# 1_0.net
KiCad netlist of a schematic drawn in Altium Designer
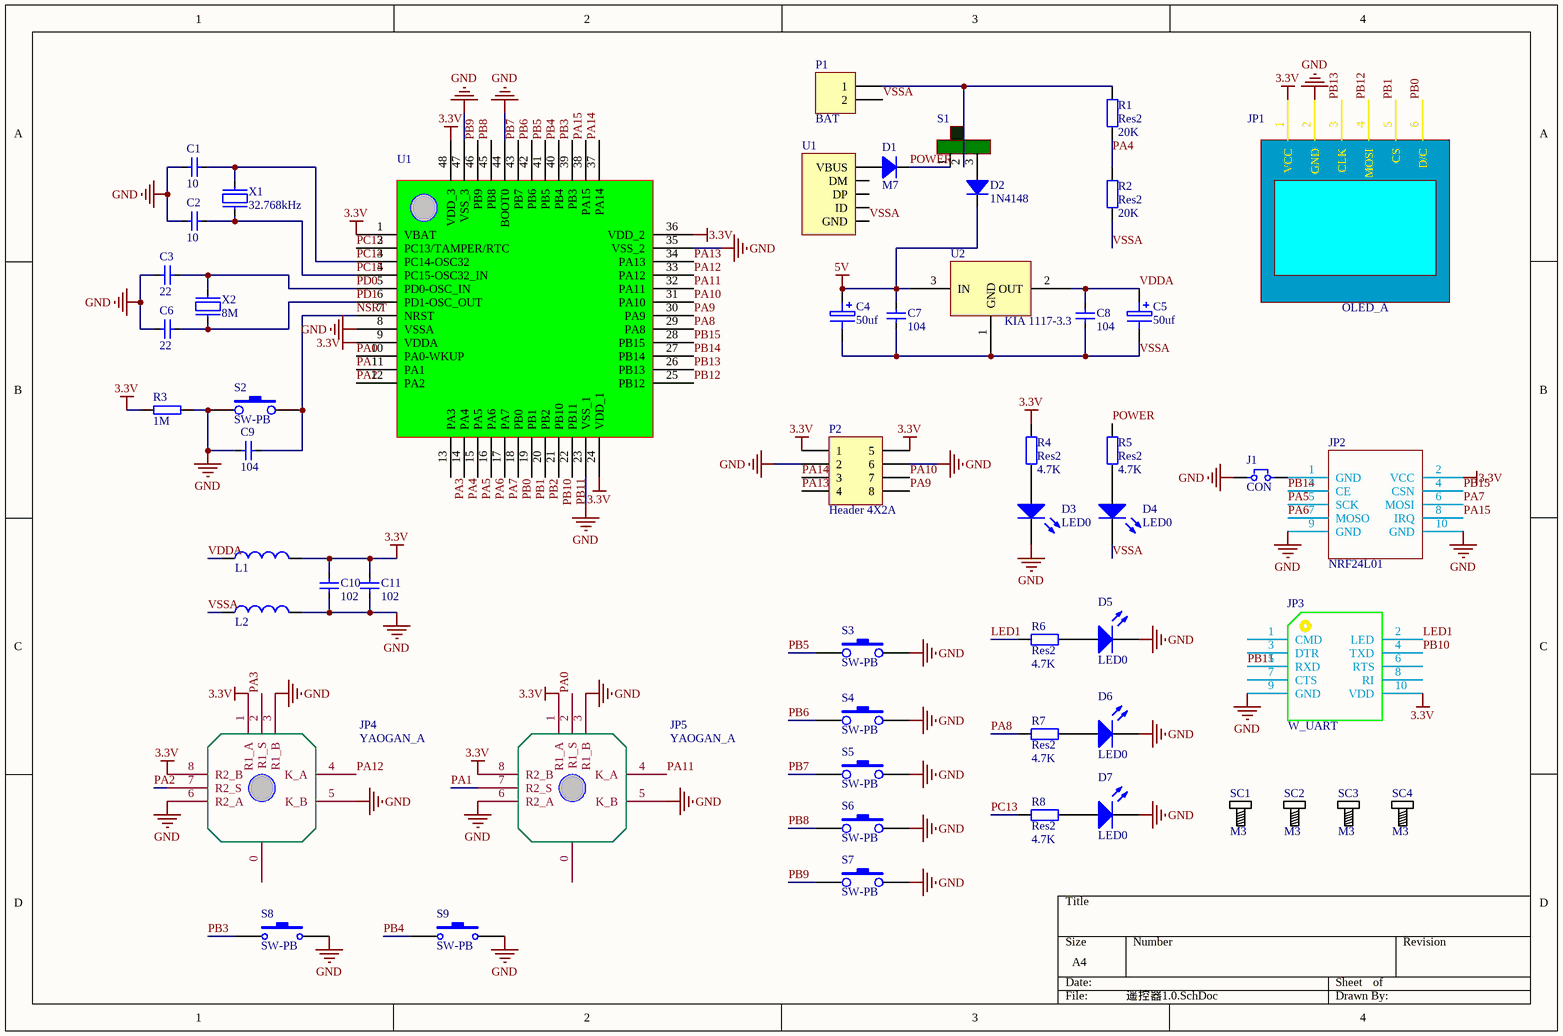
[diagram p0: 遥控器1.0.SchDoc]

(export (version "E")
  (design (tool "Eeschema 10.0.6"))
  (components
    (comp (ref "C1")
      (value "CAP_22")
      (footprint "0805-C")
      (fields (field (name "ALTIUM_UNNAMED_1") "10"))
      (libsource (lib "Flyking 常用元件") (part "CAP_22"))
    )
    (comp (ref "C2")
      (value "CAP_22")
      (footprint "0805-C")
      (fields (field (name "ALTIUM_UNNAMED_1") "10"))
      (libsource (lib "Flyking 常用元件") (part "CAP_22"))
    )
    (comp (ref "C3")
      (value "CAP_22")
      (footprint "0805-C")
      (fields (field (name "ALTIUM_UNNAMED_1") "22"))
      (libsource (lib "Flyking 常用元件") (part "CAP_22"))
    )
    (comp (ref "C4")
      (value "CAPE_10uf")
      (footprint "CAP_7*7")
      (fields (field (name "ALTIUM_UNNAMED_1") "50uf"))
      (libsource (lib "Flyking 常用元件") (part "CAPE_10uf"))
    )
    (comp (ref "C5")
      (value "CAPE_10uf")
      (footprint "CAP_7*7")
      (fields (field (name "ALTIUM_UNNAMED_1") "50uf"))
      (libsource (lib "Flyking 常用元件") (part "CAPE_10uf"))
    )
    (comp (ref "C6")
      (value "CAP_22")
      (footprint "0805-C")
      (fields (field (name "ALTIUM_UNNAMED_1") "22"))
      (libsource (lib "Flyking 常用元件") (part "CAP_22"))
    )
    (comp (ref "C7")
      (value "CAP_22")
      (footprint "0805-C")
      (fields (field (name "ALTIUM_UNNAMED_1") "104"))
      (libsource (lib "Flyking 常用元件") (part "CAP_22"))
    )
    (comp (ref "C8")
      (value "CAP_22")
      (footprint "0805-C")
      (fields (field (name "ALTIUM_UNNAMED_1") "104"))
      (libsource (lib "Flyking 常用元件") (part "CAP_22"))
    )
    (comp (ref "C9")
      (value "CAP_22")
      (footprint "0805-C")
      (fields (field (name "ALTIUM_UNNAMED_1") "104"))
      (libsource (lib "Flyking 常用元件") (part "CAP_22"))
    )
    (comp (ref "C10")
      (value "CAP_22")
      (footprint "0805-C")
      (fields (field (name "ALTIUM_UNNAMED_1") "102"))
      (libsource (lib "Flyking 常用元件") (part "CAP_22"))
    )
    (comp (ref "C11")
      (value "CAP_22")
      (footprint "0805-C")
      (fields (field (name "ALTIUM_UNNAMED_1") "102"))
      (libsource (lib "Flyking 常用元件") (part "CAP_22"))
    )
    (comp (ref "D1") (value "M7") (footprint "D_214A") (libsource (lib "xl_lib_v_2") (part "1N4148")))
    (comp (ref "D2") (value "1N4148") (footprint "D_214A") (libsource (lib "xl_lib_v_2") (part "1N4148")))
    (comp (ref "D3")
      (value "LED0")
      (footprint "0805-LED")
      (description "Typical INFRARED GaAs LED")
      (fields (field (name "PUBLISHER") "Altium Limited"))
      (libsource (lib "Miscellaneous Devices") (part "LED0"))
    )
    (comp (ref "D4")
      (value "LED0")
      (footprint "0805-LED")
      (description "Typical INFRARED GaAs LED")
      (fields (field (name "PUBLISHER") "Altium Limited"))
      (libsource (lib "Miscellaneous Devices") (part "LED0"))
    )
    (comp (ref "D5")
      (value "LED0")
      (footprint "0805-LED")
      (description "Typical INFRARED GaAs LED")
      (fields (field (name "PUBLISHER") "Altium Limited"))
      (libsource (lib "Miscellaneous Devices") (part "LED0"))
    )
    (comp (ref "D6")
      (value "LED0")
      (footprint "0805-LED")
      (description "Typical INFRARED GaAs LED")
      (fields (field (name "PUBLISHER") "Altium Limited"))
      (libsource (lib "Miscellaneous Devices") (part "LED0"))
    )
    (comp (ref "D7")
      (value "LED0")
      (footprint "0805-LED")
      (description "Typical INFRARED GaAs LED")
      (fields (field (name "PUBLISHER") "Altium Limited"))
      (libsource (lib "Miscellaneous Devices") (part "LED0"))
    )
    (comp (ref "J1")
      (value "CON")
      (footprint "HDR1X2-2.54")
      (libsource (lib "xl_lib_v_1") (part "JAP-HEADER2"))
    )
    (comp (ref "JP1") (value "OLED_A") (footprint "OLED-18*17") (libsource (lib "OLED") (part "OLED_A")))
    (comp (ref "JP2")
      (value "NRF24L01")
      (footprint "NRF24L01_A")
      (libsource (lib "NRF24L01") (part "NRF24L01"))
    )
    (comp (ref "JP3") (value "W_UART") (footprint "S-UART") (libsource (lib "S_USRT") (part "W_UART")))
    (comp (ref "JP4")
      (value "YAOGAN_A")
      (footprint "YAOGAN_A")
      (libsource (lib "SCH_IPC7_LC") (part "YAOGAN_A"))
    )
    (comp (ref "JP5")
      (value "YAOGAN_A")
      (footprint "YAOGAN_A")
      (libsource (lib "SCH_IPC7_LC") (part "YAOGAN_A"))
    )
    (comp (ref "L1") (value "L_") (footprint "0805") (libsource (lib "Flyking 常用元件") (part "L_")))
    (comp (ref "L2") (value "L_") (footprint "0805") (libsource (lib "Flyking 常用元件") (part "L_")))
    (comp (ref "P1")
      (value "BAT")
      (footprint "3.2X1.6X1.1")
      (description "Header, 2-Pin")
      (fields (field (name "PUBLISHER") "Altium Limited"))
      (libsource (lib "Miscellaneous Connectors") (part "Header 2"))
    )
    (comp (ref "P2")
      (value "Header 4X2A")
      (footprint "HDR2X4_CEN")
      (description "Header, 4-Pin, Dual row")
      (fields (field (name "PUBLISHER") "Altium Limited"))
      (libsource (lib "Miscellaneous Connectors") (part "Header 4X2A"))
    )
    (comp (ref "R1")
      (value "Res2")
      (footprint "0805-R")
      (description "Resistor")
      (fields (field (name "ALTIUM_VALUE") "20K") (field (name "PUBLISHER") "Altium Limited"))
      (libsource (lib "Miscellaneous Devices") (part "Res2"))
    )
    (comp (ref "R2")
      (value "Res2")
      (footprint "0805-R")
      (description "Resistor")
      (fields (field (name "ALTIUM_VALUE") "20K") (field (name "PUBLISHER") "Altium Limited"))
      (libsource (lib "Miscellaneous Devices") (part "Res2"))
    )
    (comp (ref "R3")
      (value "RES_10K")
      (footprint "0805-R")
      (fields (field (name "ALTIUM_UNNAMED_1") "1M"))
      (libsource (lib "Flyking 常用元件") (part "RES_10K"))
    )
    (comp (ref "R4")
      (value "Res2")
      (footprint "0805-R")
      (description "Resistor")
      (fields (field (name "ALTIUM_VALUE") "4.7K") (field (name "PUBLISHER") "Altium Limited"))
      (libsource (lib "") (part "Res2_1"))
    )
    (comp (ref "R5")
      (value "Res2")
      (footprint "0805-R")
      (description "Resistor")
      (fields (field (name "ALTIUM_VALUE") "4.7K") (field (name "PUBLISHER") "Altium Limited"))
      (libsource (lib "") (part "Res2_1"))
    )
    (comp (ref "R6")
      (value "Res2")
      (footprint "0805-R")
      (description "Resistor")
      (fields (field (name "ALTIUM_VALUE") "4.7K") (field (name "PUBLISHER") "Altium Limited"))
      (libsource (lib "") (part "Res2_2"))
    )
    (comp (ref "R7")
      (value "Res2")
      (footprint "0805-R")
      (description "Resistor")
      (fields (field (name "ALTIUM_VALUE") "4.7K") (field (name "PUBLISHER") "Altium Limited"))
      (libsource (lib "") (part "Res2_2"))
    )
    (comp (ref "R8")
      (value "Res2")
      (footprint "0805-R")
      (description "Resistor")
      (fields (field (name "ALTIUM_VALUE") "4.7K") (field (name "PUBLISHER") "Altium Limited"))
      (libsource (lib "") (part "Res2_2"))
    )
    (comp (ref "S1")
      (value "SS12D07-1P2T")
      (footprint "SS12D07-1")
      (libsource (lib "xl_lib_v_1") (part "SS12D07"))
    )
    (comp (ref "S2") (value "SW-PB") (footprint "SW-SMD-T") (libsource (lib "SW开关") (part "SW-PB")))
    (comp (ref "S3") (value "SW-PB") (footprint "KEY-SMD") (libsource (lib "SW开关") (part "SW-PB")))
    (comp (ref "S4") (value "SW-PB") (footprint "KEY-SMD") (libsource (lib "SW开关") (part "SW-PB")))
    (comp (ref "S5") (value "SW-PB") (footprint "KEY-SMD") (libsource (lib "SW开关") (part "SW-PB")))
    (comp (ref "S6") (value "SW-PB") (footprint "KEY-SMD") (libsource (lib "SW开关") (part "SW-PB")))
    (comp (ref "S7") (value "SW-PB") (footprint "KEY-SMD") (libsource (lib "SW开关") (part "SW-PB")))
    (comp (ref "S8")
      (value "SW-PB")
      (footprint "KEY-4B")
      (description "Switch")
      (fields (field (name "PUBLISHER") "Altium Limited"))
      (libsource (lib "Miscellaneous Devices") (part "SW-PB"))
    )
    (comp (ref "S9")
      (value "SW-PB")
      (footprint "KEY-4B")
      (description "Switch")
      (fields (field (name "PUBLISHER") "Altium Limited"))
      (libsource (lib "Miscellaneous Devices") (part "SW-PB"))
    )
    (comp (ref "SC1")
      (value "M3")
      (footprint "TZ-M3")
      (description "Screw")
      (libsource (lib "SCH_Other") (part "Screw_M3"))
    )
    (comp (ref "SC2")
      (value "M3")
      (footprint "TZ-M3")
      (description "Screw")
      (libsource (lib "SCH_Other") (part "Screw_M3"))
    )
    (comp (ref "SC3")
      (value "M3")
      (footprint "TZ-M3")
      (description "Screw")
      (libsource (lib "SCH_Other") (part "Screw_M3"))
    )
    (comp (ref "SC4")
      (value "M3")
      (footprint "TZ-M3")
      (description "Screw")
      (libsource (lib "SCH_Other") (part "Screw_M3"))
    )
    (comp (ref "U1")
      (value "USB_Micro")
      (footprint "USB_MINI_B")
      (description "USB")
      (libsource (lib "SCH_USB") (part "USB_Micro"))
    )
    (comp (ref "U2")
      (value "KIA 1117-3.3")
      (footprint "SOT-223")
      (fields (field (name "ALTIUM_UNNAMED_1") "KIA 1117-3.3"))
      (libsource (lib "Flyking 常用元件") (part "KIA 1117-3.3"))
    )
    (comp (ref "U3")
      (value "U1")
      (footprint "LQFP48_L")
      (description "STM32F103C8T6")
      (libsource (lib "STM32F103C8T6") (part "Component_1"))
    )
    (comp (ref "X1")
      (value "XTAL")
      (footprint "XO-3*8")
      (fields (field (name "ALTIUM_UNNAMED_1") "32.768kHz"))
      (libsource (lib "Flyking 常用元件") (part "XTAL"))
    )
    (comp (ref "X2")
      (value "XTAL")
      (footprint "HC-49")
      (fields (field (name "ALTIUM_UNNAMED_1") "8M"))
      (libsource (lib "Flyking 常用元件") (part "XTAL"))
    )
  )
  (nets
    (net (code "1") (name "/LED1") (class "Default")
      (node (ref "JP3") (pin "2") (pinfunction "LED_2") (pintype "passive"))
      (node (ref "R6") (pin "1") (pinfunction "1_1") (pintype "passive"))
    )
    (net (code "2") (name "/NSRT") (class "Default")
      (node (ref "C9") (pin "2") (pintype "passive"))
      (node (ref "S2") (pin "2") (pinfunction "2_2") (pintype "passive"))
      (node (ref "U3") (pin "7") (pinfunction "NRST_7") (pintype "passive"))
    )
    (net (code "3") (name "/PA0") (class "Default")
      (node (ref "JP5") (pin "2") (pinfunction "R1_S_2") (pintype "passive"))
      (node (ref "U3") (pin "10") (pinfunction "PA0-WKUP_10") (pintype "passive"))
    )
    (net (code "4") (name "/PA1") (class "Default")
      (node (ref "JP5") (pin "7") (pinfunction "R2_S_7") (pintype "passive"))
      (node (ref "U3") (pin "11") (pinfunction "PA1_11") (pintype "passive"))
    )
    (net (code "5") (name "/PA2") (class "Default")
      (node (ref "JP4") (pin "7") (pinfunction "R2_S_7") (pintype "passive"))
      (node (ref "U3") (pin "12") (pinfunction "PA2_12") (pintype "passive"))
    )
    (net (code "6") (name "/PA3") (class "Default")
      (node (ref "JP4") (pin "2") (pinfunction "R1_S_2") (pintype "passive"))
      (node (ref "U3") (pin "13") (pinfunction "PA3_13") (pintype "passive"))
    )
    (net (code "7") (name "/PA4") (class "Default")
      (node (ref "R1") (pin "1") (pinfunction "1_1") (pintype "passive"))
      (node (ref "R2") (pin "2") (pinfunction "2_2") (pintype "passive"))
      (node (ref "U3") (pin "14") (pinfunction "PA4_14") (pintype "passive"))
    )
    (net (code "8") (name "/PA5") (class "Default")
      (node (ref "JP2") (pin "5") (pinfunction "SCK_5") (pintype "passive"))
      (node (ref "U3") (pin "15") (pinfunction "PA5_15") (pintype "passive"))
    )
    (net (code "9") (name "/PA6") (class "Default")
      (node (ref "JP2") (pin "7") (pinfunction "MOSO_7") (pintype "passive"))
      (node (ref "U3") (pin "16") (pinfunction "PA6_16") (pintype "passive"))
    )
    (net (code "10") (name "/PA7") (class "Default")
      (node (ref "JP2") (pin "6") (pinfunction "MOSI_6") (pintype "passive"))
      (node (ref "U3") (pin "17") (pinfunction "PA7_17") (pintype "passive"))
    )
    (net (code "11") (name "/PA8") (class "Default")
      (node (ref "R7") (pin "1") (pinfunction "1_1") (pintype "passive"))
      (node (ref "U3") (pin "29") (pinfunction "PA8_29") (pintype "passive"))
    )
    (net (code "12") (name "/PA9") (class "Default")
      (node (ref "P2") (pin "8") (pinfunction "8_8") (pintype "passive"))
      (node (ref "U3") (pin "30") (pinfunction "PA9_30") (pintype "passive"))
    )
    (net (code "13") (name "/PA10") (class "Default")
      (node (ref "P2") (pin "7") (pinfunction "7_7") (pintype "passive"))
      (node (ref "U3") (pin "31") (pinfunction "PA10_31") (pintype "passive"))
    )
    (net (code "14") (name "/PA11") (class "Default")
      (node (ref "JP5") (pin "4") (pinfunction "K_A_4") (pintype "passive"))
      (node (ref "U3") (pin "32") (pinfunction "PA11_32") (pintype "passive"))
    )
    (net (code "15") (name "/PA12") (class "Default")
      (node (ref "JP4") (pin "4") (pinfunction "K_A_4") (pintype "passive"))
      (node (ref "U3") (pin "33") (pinfunction "PA12_33") (pintype "passive"))
    )
    (net (code "16") (name "/PA13") (class "Default")
      (node (ref "P2") (pin "4") (pinfunction "4_4") (pintype "passive"))
      (node (ref "U3") (pin "34") (pinfunction "PA13_34") (pintype "passive"))
    )
    (net (code "17") (name "/PA14") (class "Default")
      (node (ref "P2") (pin "3") (pinfunction "3_3") (pintype "passive"))
      (node (ref "U3") (pin "37") (pinfunction "PA14_37") (pintype "passive"))
    )
    (net (code "18") (name "/PA15") (class "Default")
      (node (ref "JP2") (pin "8") (pinfunction "IRQ_8") (pintype "passive"))
      (node (ref "U3") (pin "38") (pinfunction "PA15_38") (pintype "passive"))
    )
    (net (code "19") (name "/PB0") (class "Default")
      (node (ref "JP1") (pin "6") (pinfunction "D/C_6") (pintype "passive"))
      (node (ref "U3") (pin "18") (pinfunction "PB0_18") (pintype "passive"))
    )
    (net (code "20") (name "/PB1") (class "Default")
      (node (ref "JP1") (pin "5") (pinfunction "CS_5") (pintype "passive"))
      (node (ref "U3") (pin "19") (pinfunction "PB1_19") (pintype "passive"))
    )
    (net (code "21") (name "/PB2") (class "Default")
      (node (ref "U3") (pin "20") (pinfunction "PB2_20") (pintype "passive"))
    )
    (net (code "22") (name "/PB3") (class "Default")
      (node (ref "S8") (pin "1") (pinfunction "1_1") (pintype "passive"))
      (node (ref "U3") (pin "39") (pinfunction "PB3_39") (pintype "passive"))
    )
    (net (code "23") (name "/PB4") (class "Default")
      (node (ref "S9") (pin "1") (pinfunction "1_1") (pintype "passive"))
      (node (ref "U3") (pin "40") (pinfunction "PB4_40") (pintype "passive"))
    )
    (net (code "24") (name "/PB5") (class "Default")
      (node (ref "S3") (pin "1") (pinfunction "1_1") (pintype "passive"))
      (node (ref "U3") (pin "41") (pinfunction "PB5_41") (pintype "passive"))
    )
    (net (code "25") (name "/PB6") (class "Default")
      (node (ref "S4") (pin "1") (pinfunction "1_1") (pintype "passive"))
      (node (ref "U3") (pin "42") (pinfunction "PB6_42") (pintype "passive"))
    )
    (net (code "26") (name "/PB7") (class "Default")
      (node (ref "S5") (pin "1") (pinfunction "1_1") (pintype "passive"))
      (node (ref "U3") (pin "43") (pinfunction "PB7_43") (pintype "passive"))
    )
    (net (code "27") (name "/PB8") (class "Default")
      (node (ref "S6") (pin "1") (pinfunction "1_1") (pintype "passive"))
      (node (ref "U3") (pin "45") (pinfunction "PB8_45") (pintype "passive"))
    )
    (net (code "28") (name "/PB9") (class "Default")
      (node (ref "S7") (pin "1") (pinfunction "1_1") (pintype "passive"))
      (node (ref "U3") (pin "46") (pinfunction "PB9_46") (pintype "passive"))
    )
    (net (code "29") (name "/PB10") (class "Default")
      (node (ref "JP3") (pin "4") (pinfunction "TXD_4") (pintype "passive"))
      (node (ref "U3") (pin "21") (pinfunction "PB10_21") (pintype "passive"))
    )
    (net (code "30") (name "/PB11") (class "Default")
      (node (ref "JP3") (pin "5") (pinfunction "RXD_5") (pintype "passive"))
      (node (ref "U3") (pin "22") (pinfunction "PB11_22") (pintype "passive"))
    )
    (net (code "31") (name "/PB12") (class "Default")
      (node (ref "JP1") (pin "4") (pinfunction "MOSI_4") (pintype "passive"))
      (node (ref "U3") (pin "25") (pinfunction "PB12_25") (pintype "passive"))
    )
    (net (code "32") (name "/PB13") (class "Default")
      (node (ref "JP1") (pin "3") (pinfunction "CLK_3") (pintype "passive"))
      (node (ref "U3") (pin "26") (pinfunction "PB13_26") (pintype "passive"))
    )
    (net (code "33") (name "/PB14") (class "Default")
      (node (ref "JP2") (pin "3") (pinfunction "CE_3") (pintype "passive"))
      (node (ref "U3") (pin "27") (pinfunction "PB14_27") (pintype "passive"))
    )
    (net (code "34") (name "/PB15") (class "Default")
      (node (ref "JP2") (pin "4") (pinfunction "CSN_4") (pintype "passive"))
      (node (ref "U3") (pin "28") (pinfunction "PB15_28") (pintype "passive"))
    )
    (net (code "35") (name "/PC13") (class "Default")
      (node (ref "R8") (pin "1") (pinfunction "1_1") (pintype "passive"))
      (node (ref "U3") (pin "2") (pinfunction "PC13/TAMPER/RTC_2") (pintype "passive"))
    )
    (net (code "36") (name "/PC14") (class "Default")
      (node (ref "C1") (pin "2") (pintype "passive"))
      (node (ref "U3") (pin "3") (pinfunction "PC14-OSC32_3") (pintype "passive"))
      (node (ref "X1") (pin "2") (pintype "passive"))
    )
    (net (code "37") (name "/PC15") (class "Default")
      (node (ref "C2") (pin "2") (pintype "passive"))
      (node (ref "U3") (pin "4") (pinfunction "PC15-OSC32_IN_4") (pintype "passive"))
      (node (ref "X1") (pin "1") (pintype "passive"))
    )
    (net (code "38") (name "/PD0") (class "Default")
      (node (ref "C3") (pin "2") (pintype "passive"))
      (node (ref "U3") (pin "5") (pinfunction "PD0-OSC_IN_5") (pintype "passive"))
      (node (ref "X2") (pin "2") (pintype "passive"))
    )
    (net (code "39") (name "/PD1") (class "Default")
      (node (ref "C6") (pin "2") (pintype "passive"))
      (node (ref "U3") (pin "6") (pinfunction "PD1-OSC_OUT_6") (pintype "passive"))
      (node (ref "X2") (pin "1") (pintype "passive"))
    )
    (net (code "40") (name "/POWER") (class "Default")
      (node (ref "D1") (pin "2") (pinfunction "K_2") (pintype "passive"))
      (node (ref "R5") (pin "1") (pinfunction "1_1") (pintype "passive"))
      (node (ref "S1") (pin "1") (pinfunction "S1_1") (pintype "passive"))
    )
    (net (code "41") (name "/VDDA") (class "Default")
      (node (ref "C5") (pin "1") (pinfunction "+_1") (pintype "passive"))
      (node (ref "C8") (pin "2") (pintype "passive"))
      (node (ref "L1") (pin "1") (pinfunction "1_1") (pintype "passive"))
      (node (ref "U2") (pin "2") (pinfunction "OUT_2") (pintype "passive"))
    )
    (net (code "42") (name "/VSSA") (class "Default")
      (node (ref "C4") (pin "2") (pinfunction "--_2") (pintype "passive"))
      (node (ref "C5") (pin "2") (pinfunction "--_2") (pintype "passive"))
      (node (ref "C7") (pin "1") (pintype "passive"))
      (node (ref "C8") (pin "1") (pintype "passive"))
      (node (ref "D4") (pin "2") (pinfunction "K_2") (pintype "passive"))
      (node (ref "L2") (pin "1") (pinfunction "1_1") (pintype "passive"))
      (node (ref "P1") (pin "2") (pinfunction "2_2") (pintype "passive"))
      (node (ref "R2") (pin "1") (pinfunction "1_1") (pintype "passive"))
      (node (ref "U1") (pin "5") (pinfunction "GND_5") (pintype "passive"))
      (node (ref "U2") (pin "1") (pinfunction "GND_1") (pintype "passive"))
    )
    (net (code "43") (name "3.3V") (class "Default")
      (node (ref "C10") (pin "2") (pintype "passive"))
      (node (ref "C11") (pin "2") (pintype "passive"))
      (node (ref "JP1") (pin "1") (pinfunction "VCC_1") (pintype "passive"))
      (node (ref "JP2") (pin "2") (pinfunction "VCC_2") (pintype "passive"))
      (node (ref "JP3") (pin "10") (pinfunction "VDD_10") (pintype "passive"))
      (node (ref "JP4") (pin "1") (pinfunction "R1_A_1") (pintype "passive"))
      (node (ref "JP4") (pin "8") (pinfunction "R2_B_8") (pintype "passive"))
      (node (ref "JP5") (pin "1") (pinfunction "R1_A_1") (pintype "passive"))
      (node (ref "JP5") (pin "8") (pinfunction "R2_B_8") (pintype "passive"))
      (node (ref "L1") (pin "2") (pinfunction "2_2") (pintype "passive"))
      (node (ref "P2") (pin "1") (pinfunction "1_1") (pintype "passive"))
      (node (ref "P2") (pin "5") (pinfunction "5_5") (pintype "passive"))
      (node (ref "R3") (pin "2") (pintype "passive"))
      (node (ref "R4") (pin "1") (pinfunction "1_1") (pintype "passive"))
      (node (ref "U3") (pin "1") (pinfunction "VBAT_1") (pintype "passive"))
      (node (ref "U3") (pin "24") (pinfunction "VDD_1_24") (pintype "passive"))
      (node (ref "U3") (pin "36") (pinfunction "VDD_2_36") (pintype "passive"))
      (node (ref "U3") (pin "48") (pinfunction "VDD_3_48") (pintype "passive"))
      (node (ref "U3") (pin "9") (pinfunction "VDDA_9") (pintype "passive"))
    )
    (net (code "44") (name "5V") (class "Default")
      (node (ref "C4") (pin "1") (pinfunction "+_1") (pintype "passive"))
      (node (ref "C7") (pin "2") (pintype "passive"))
      (node (ref "D2") (pin "2") (pinfunction "K_2") (pintype "passive"))
      (node (ref "U2") (pin "3") (pinfunction "IN_3") (pintype "passive"))
    )
    (net (code "45") (name "GND") (class "Default")
      (node (ref "C1") (pin "1") (pintype "passive"))
      (node (ref "C10") (pin "1") (pintype "passive"))
      (node (ref "C11") (pin "1") (pintype "passive"))
      (node (ref "C2") (pin "1") (pintype "passive"))
      (node (ref "C3") (pin "1") (pintype "passive"))
      (node (ref "C6") (pin "1") (pintype "passive"))
      (node (ref "C9") (pin "1") (pintype "passive"))
      (node (ref "D3") (pin "2") (pinfunction "K_2") (pintype "passive"))
      (node (ref "D5") (pin "2") (pinfunction "K_2") (pintype "passive"))
      (node (ref "D6") (pin "2") (pinfunction "K_2") (pintype "passive"))
      (node (ref "D7") (pin "2") (pinfunction "K_2") (pintype "passive"))
      (node (ref "J1") (pin "1") (pinfunction "1_1") (pintype "passive"))
      (node (ref "JP1") (pin "2") (pinfunction "GND_2") (pintype "passive"))
      (node (ref "JP2") (pin "10") (pinfunction "GND_10") (pintype "passive"))
      (node (ref "JP2") (pin "9") (pinfunction "GND_9") (pintype "passive"))
      (node (ref "JP3") (pin "9") (pinfunction "GND_9") (pintype "passive"))
      (node (ref "JP4") (pin "3") (pinfunction "R1_B_3") (pintype "passive"))
      (node (ref "JP4") (pin "5") (pinfunction "K_B_5") (pintype "passive"))
      (node (ref "JP4") (pin "6") (pinfunction "R2_A_6") (pintype "passive"))
      (node (ref "JP5") (pin "3") (pinfunction "R1_B_3") (pintype "passive"))
      (node (ref "JP5") (pin "5") (pinfunction "K_B_5") (pintype "passive"))
      (node (ref "JP5") (pin "6") (pinfunction "R2_A_6") (pintype "passive"))
      (node (ref "L2") (pin "2") (pinfunction "2_2") (pintype "passive"))
      (node (ref "P2") (pin "2") (pinfunction "2_2") (pintype "passive"))
      (node (ref "P2") (pin "6") (pinfunction "6_6") (pintype "passive"))
      (node (ref "R3") (pin "1") (pintype "passive"))
      (node (ref "S2") (pin "1") (pinfunction "1_1") (pintype "passive"))
      (node (ref "S3") (pin "2") (pinfunction "2_2") (pintype "passive"))
      (node (ref "S4") (pin "2") (pinfunction "2_2") (pintype "passive"))
      (node (ref "S5") (pin "2") (pinfunction "2_2") (pintype "passive"))
      (node (ref "S6") (pin "2") (pinfunction "2_2") (pintype "passive"))
      (node (ref "S7") (pin "2") (pinfunction "2_2") (pintype "passive"))
      (node (ref "S8") (pin "2") (pinfunction "2_2") (pintype "passive"))
      (node (ref "S9") (pin "2") (pinfunction "2_2") (pintype "passive"))
      (node (ref "U3") (pin "23") (pinfunction "VSS_1_23") (pintype "passive"))
      (node (ref "U3") (pin "35") (pinfunction "VSS_2_35") (pintype "passive"))
      (node (ref "U3") (pin "44") (pinfunction "BOOT0_44") (pintype "passive"))
      (node (ref "U3") (pin "47") (pinfunction "VSS_3_47") (pintype "passive"))
      (node (ref "U3") (pin "8") (pinfunction "VSSA_8") (pintype "passive"))
    )
    (net (code "46") (name "Net-(D1-A)") (class "Default")
      (node (ref "D1") (pin "1") (pinfunction "A_1") (pintype "passive"))
      (node (ref "U1") (pin "1") (pinfunction "VBUS_1") (pintype "passive"))
    )
    (net (code "47") (name "Net-(D2-A)") (class "Default")
      (node (ref "D2") (pin "1") (pinfunction "A_1") (pintype "passive"))
      (node (ref "S1") (pin "3") (pinfunction "S3_3") (pintype "passive"))
    )
    (net (code "48") (name "Net-(D3-A)") (class "Default")
      (node (ref "D3") (pin "1") (pinfunction "A_1") (pintype "passive"))
      (node (ref "R4") (pin "2") (pinfunction "2_2") (pintype "passive"))
    )
    (net (code "49") (name "Net-(D4-A)") (class "Default")
      (node (ref "D4") (pin "1") (pinfunction "A_1") (pintype "passive"))
      (node (ref "R5") (pin "2") (pinfunction "2_2") (pintype "passive"))
    )
    (net (code "50") (name "Net-(D5-A)") (class "Default")
      (node (ref "D5") (pin "1") (pinfunction "A_1") (pintype "passive"))
      (node (ref "R6") (pin "2") (pinfunction "2_2") (pintype "passive"))
    )
    (net (code "51") (name "Net-(D6-A)") (class "Default")
      (node (ref "D6") (pin "1") (pinfunction "A_1") (pintype "passive"))
      (node (ref "R7") (pin "2") (pinfunction "2_2") (pintype "passive"))
    )
    (net (code "52") (name "Net-(D7-A)") (class "Default")
      (node (ref "D7") (pin "1") (pinfunction "A_1") (pintype "passive"))
      (node (ref "R8") (pin "2") (pinfunction "2_2") (pintype "passive"))
    )
    (net (code "53") (name "Net-(J1-Pad2)") (class "Default")
      (node (ref "J1") (pin "2") (pinfunction "2_2") (pintype "passive"))
      (node (ref "JP2") (pin "1") (pinfunction "GND_1") (pintype "passive"))
    )
    (net (code "54") (name "Net-(S1-S2)") (class "Default")
      (node (ref "P1") (pin "1") (pinfunction "1_1") (pintype "passive"))
      (node (ref "R1") (pin "2") (pinfunction "2_2") (pintype "passive"))
      (node (ref "S1") (pin "2") (pinfunction "S2_2") (pintype "passive"))
    )
    (net (code "55") (name "unconnected-(JP3-CMD-Pad1)") (class "Default")
      (node (ref "JP3") (pin "1") (pinfunction "CMD_1") (pintype "passive"))
    )
    (net (code "56") (name "unconnected-(JP3-CTS-Pad7)") (class "Default")
      (node (ref "JP3") (pin "7") (pinfunction "CTS_7") (pintype "passive"))
    )
    (net (code "57") (name "unconnected-(JP3-DTR-Pad3)") (class "Default")
      (node (ref "JP3") (pin "3") (pinfunction "DTR_3") (pintype "passive"))
    )
    (net (code "58") (name "unconnected-(JP3-RI-Pad8)") (class "Default")
      (node (ref "JP3") (pin "8") (pinfunction "RI_8") (pintype "passive"))
    )
    (net (code "59") (name "unconnected-(JP3-RTS-Pad6)") (class "Default")
      (node (ref "JP3") (pin "6") (pinfunction "RTS_6") (pintype "passive"))
    )
    (net (code "60") (name "unconnected-(JP4-Pad0)") (class "Default")
      (node (ref "JP4") (pin "0") (pintype "passive"))
    )
    (net (code "61") (name "unconnected-(JP5-Pad0)") (class "Default")
      (node (ref "JP5") (pin "0") (pintype "passive"))
    )
    (net (code "62") (name "unconnected-(U1-DM-Pad2)") (class "Default")
      (node (ref "U1") (pin "2") (pinfunction "DM_2") (pintype "passive"))
    )
    (net (code "63") (name "unconnected-(U1-DP-Pad3)") (class "Default")
      (node (ref "U1") (pin "3") (pinfunction "DP_3") (pintype "passive"))
    )
    (net (code "64") (name "unconnected-(U1-ID-Pad4)") (class "Default")
      (node (ref "U1") (pin "4") (pinfunction "ID_4") (pintype "passive"))
    )
  )
)
